# 5V_Regulator.net
KiCad netlist of a schematic drawn in Altium Designer
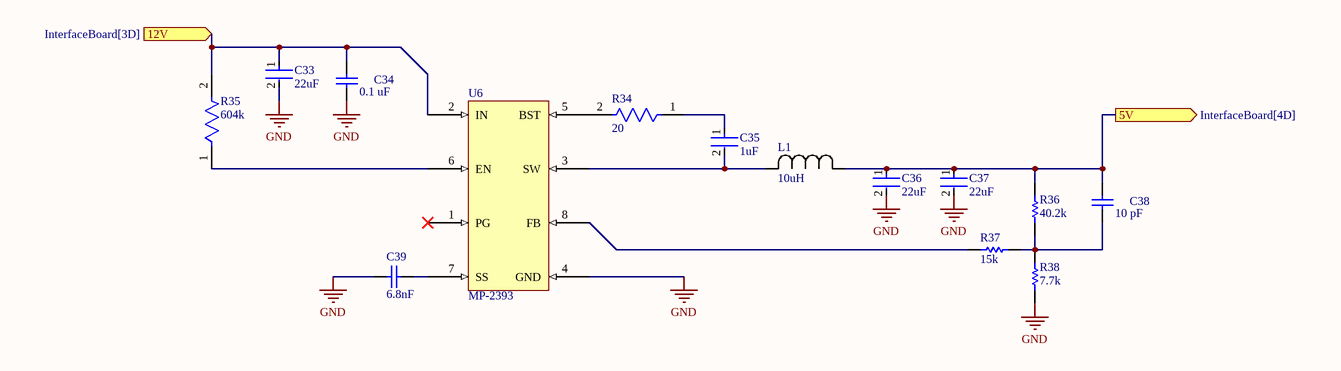
[diagram p0: 5V Regulator.SchDoc]

(export (version "E")
  (design (tool "Eeschema 10.0.6"))
  (components
    (comp (ref "C33")
      (value "22uF")
      (footprint "FP-0603-L_1_6_0_2-W_0_8_0-IPC_B")
      (description "0603")
      (fields (field (name "TOLERANCE") "20%"))
      (libsource (lib "Altium Content Vault") (part "b4654b650e69147ec39a6b967a45e02"))
    )
    (comp (ref "C34")
      (value "0.1 uF")
      (footprint "CAPC1608X90X35NL15T15")
      (description "0603 (1608 metric)")
      (fields
        (field (name "MANUFACTURER") "AVX Interconnect / Elco")
        (field (name "PART NUMBER") "LD033C104KAB2A")
      )
      (libsource (lib "Altium Content Vault") (part "CAP"))
    )
    (comp (ref "C35")
      (value "1uF")
      (footprint "FP-0603-L_1_6_0_15-W_0_8-IPC_B")
      (description "None")
      (fields (field (name "TOLERANCE") "20%"))
      (libsource (lib "Altium Content Vault") (part "b4654b650e69147ec39a6b967a45e02"))
    )
    (comp (ref "C36")
      (value "22uF")
      (footprint "FP-0603-L_1_6_0_2-W_0_8_0-IPC_B")
      (description "0603")
      (fields (field (name "TOLERANCE") "20%"))
      (libsource (lib "Altium Content Vault") (part "b4654b650e69147ec39a6b967a45e02"))
    )
    (comp (ref "C37")
      (value "22uF")
      (footprint "FP-0603-L_1_6_0_2-W_0_8_0-IPC_B")
      (description "0603")
      (fields (field (name "TOLERANCE") "20%"))
      (libsource (lib "Altium Content Vault") (part "b4654b650e69147ec39a6b967a45e02"))
    )
    (comp (ref "C38")
      (value "10 pF")
      (footprint "CAPC1608X90X35NL15T15")
      (description "0603 (1608 metric)")
      (fields
        (field (name "MANUFACTURER") "AVX Interconnect / Elco")
        (field (name "PART NUMBER") "LD033C104KAB2A")
      )
      (libsource (lib "Altium Content Vault") (part "CAP"))
    )
    (comp (ref "C39")
      (value "6.8nF")
      (footprint "CAPC1608X90X35NL15T15")
      (description "0603 (1608 metric)")
      (fields
        (field (name "MANUFACTURER") "AVX Interconnect / Elco")
        (field (name "PART NUMBER") "LD033C104KAB2A")
      )
      (libsource (lib "Altium Content Vault") (part "CAP"))
    )
    (comp (ref "L1")
      (value "10uH")
      (footprint "IND_TAIYO_NR8040_TAY")
      (description "No Description Available")
      (fields
        (field (name "MANUFACTURER_PART_NUMBER") "NR8040T100M")
        (field (name "COPYRIGHT") "Copyright (C) 2025 Ultra Librarian. All rights reserved.")
      )
      (libsource (lib "AutoLidar_VIP_Spring25") (part "NR8040T100M"))
    )
    (comp (ref "R34")
      (value "20")
      (footprint "FP-RT0603-MFG")
      (description "RES SMD 604K OHM 1% 1/10W 0603")
      (fields
        (field (name "MANUFACTURER PART NUMBER") "RT0603FRE07604KL")
        (field (name "MANUFACTURER") "Yageo")
      )
      (libsource (lib "Altium Content Vault") (part "1029c3af85768c4190bb7ad29bc67b5"))
    )
    (comp (ref "R35")
      (value "604k")
      (footprint "FP-RT0603-MFG")
      (description "RES SMD 604K OHM 1% 1/10W 0603")
      (fields
        (field (name "MANUFACTURER PART NUMBER") "RT0603FRE07604KL")
        (field (name "MANUFACTURER") "Yageo")
      )
      (libsource (lib "Altium Content Vault") (part "1029c3af85768c4190bb7ad29bc67b5"))
    )
    (comp (ref "R36")
      (value "40.2k")
      (footprint "RESC1609X55X30ML10T20")
      (description "0603")
      (fields (field (name "MANUFACTURER") "Vishay Dale") (field (name "PART NUMBER") "TNPW060313K3BEEA"))
      (libsource (lib "Altium Content Vault") (part "RES"))
    )
    (comp (ref "R37")
      (value "15k")
      (footprint "RESC1609X55X30ML10T20")
      (description "0603")
      (fields (field (name "MANUFACTURER") "Vishay Dale") (field (name "PART NUMBER") "TNPW060313K3BEEA"))
      (libsource (lib "Altium Content Vault") (part "RES"))
    )
    (comp (ref "R38")
      (value "7.7k")
      (footprint "RESC1609X55X30ML10T20")
      (description "0603")
      (fields (field (name "MANUFACTURER") "Vishay Dale") (field (name "PART NUMBER") "TNPW060313K3BEEA"))
      (libsource (lib "Altium Content Vault") (part "RES"))
    )
    (comp (ref "U6")
      (value "MP-2393")
      (footprint "MP-2393")
      (libsource (lib "AutoLidar_VIP_Spring25") (part "MP-2393"))
    )
  )
  (nets
    (net (code "1") (name "/5V") (class "Default")
      (node (ref "C36") (pin "1") (pinfunction "1_1") (pintype "passive"))
      (node (ref "C37") (pin "1") (pinfunction "1_1") (pintype "passive"))
      (node (ref "C38") (pin "2") (pinfunction "2_2") (pintype "passive"))
      (node (ref "L1") (pin "1") (pinfunction "1_1") (pintype "passive"))
      (node (ref "R36") (pin "2") (pinfunction "2_2") (pintype "passive"))
    )
    (net (code "2") (name "/12V") (class "Default")
      (node (ref "C33") (pin "1") (pinfunction "1_1") (pintype "passive"))
      (node (ref "C34") (pin "2") (pinfunction "2_2") (pintype "passive"))
      (node (ref "R35") (pin "2") (pinfunction "2_2") (pintype "passive"))
      (node (ref "U6") (pin "2") (pinfunction "IN_2") (pintype "input"))
    )
    (net (code "3") (name "GND") (class "Default")
      (node (ref "C33") (pin "2") (pinfunction "2_2") (pintype "passive"))
      (node (ref "C34") (pin "1") (pinfunction "1_1") (pintype "passive"))
      (node (ref "C36") (pin "2") (pinfunction "2_2") (pintype "passive"))
      (node (ref "C37") (pin "2") (pinfunction "2_2") (pintype "passive"))
      (node (ref "C39") (pin "1") (pinfunction "1_1") (pintype "passive"))
      (node (ref "R38") (pin "1") (pinfunction "1_1") (pintype "passive"))
      (node (ref "U6") (pin "4") (pinfunction "GND_4") (pintype "input"))
    )
    (net (code "4") (name "Net-(C35-Pad1)") (class "Default")
      (node (ref "C35") (pin "1") (pinfunction "1_1") (pintype "passive"))
      (node (ref "R34") (pin "1") (pinfunction "1_1") (pintype "passive"))
    )
    (net (code "5") (name "Net-(C38-Pad1)") (class "Default")
      (node (ref "C38") (pin "1") (pinfunction "1_1") (pintype "passive"))
      (node (ref "R36") (pin "1") (pinfunction "1_1") (pintype "passive"))
      (node (ref "R37") (pin "2") (pinfunction "2_2") (pintype "passive"))
      (node (ref "R38") (pin "2") (pinfunction "2_2") (pintype "passive"))
    )
    (net (code "6") (name "Net-(U6-BST)") (class "Default")
      (node (ref "R34") (pin "2") (pinfunction "2_2") (pintype "passive"))
      (node (ref "U6") (pin "5") (pinfunction "BST_5") (pintype "input"))
    )
    (net (code "7") (name "Net-(U6-EN)") (class "Default")
      (node (ref "R35") (pin "1") (pinfunction "1_1") (pintype "passive"))
      (node (ref "U6") (pin "6") (pinfunction "EN_6") (pintype "input"))
    )
    (net (code "8") (name "Net-(U6-FB)") (class "Default")
      (node (ref "R37") (pin "1") (pinfunction "1_1") (pintype "passive"))
      (node (ref "U6") (pin "8") (pinfunction "FB_8") (pintype "input"))
    )
    (net (code "9") (name "Net-(U6-SS)") (class "Default")
      (node (ref "C39") (pin "2") (pinfunction "2_2") (pintype "passive"))
      (node (ref "U6") (pin "7") (pinfunction "SS_7") (pintype "input"))
    )
    (net (code "10") (name "Net-(U6-SW)") (class "Default")
      (node (ref "C35") (pin "2") (pinfunction "2_2") (pintype "passive"))
      (node (ref "L1") (pin "2") (pinfunction "2_2") (pintype "passive"))
      (node (ref "U6") (pin "3") (pinfunction "SW_3") (pintype "input"))
    )
    (net (code "11") (name "unconnected-(U6-PG-Pad1)") (class "Default")
      (node (ref "U6") (pin "1") (pinfunction "PG_1") (pintype "input+no_connect"))
    )
  )
)
